# BL600CommunicationBoard.net
KiCad netlist of a schematic drawn in EAGLE
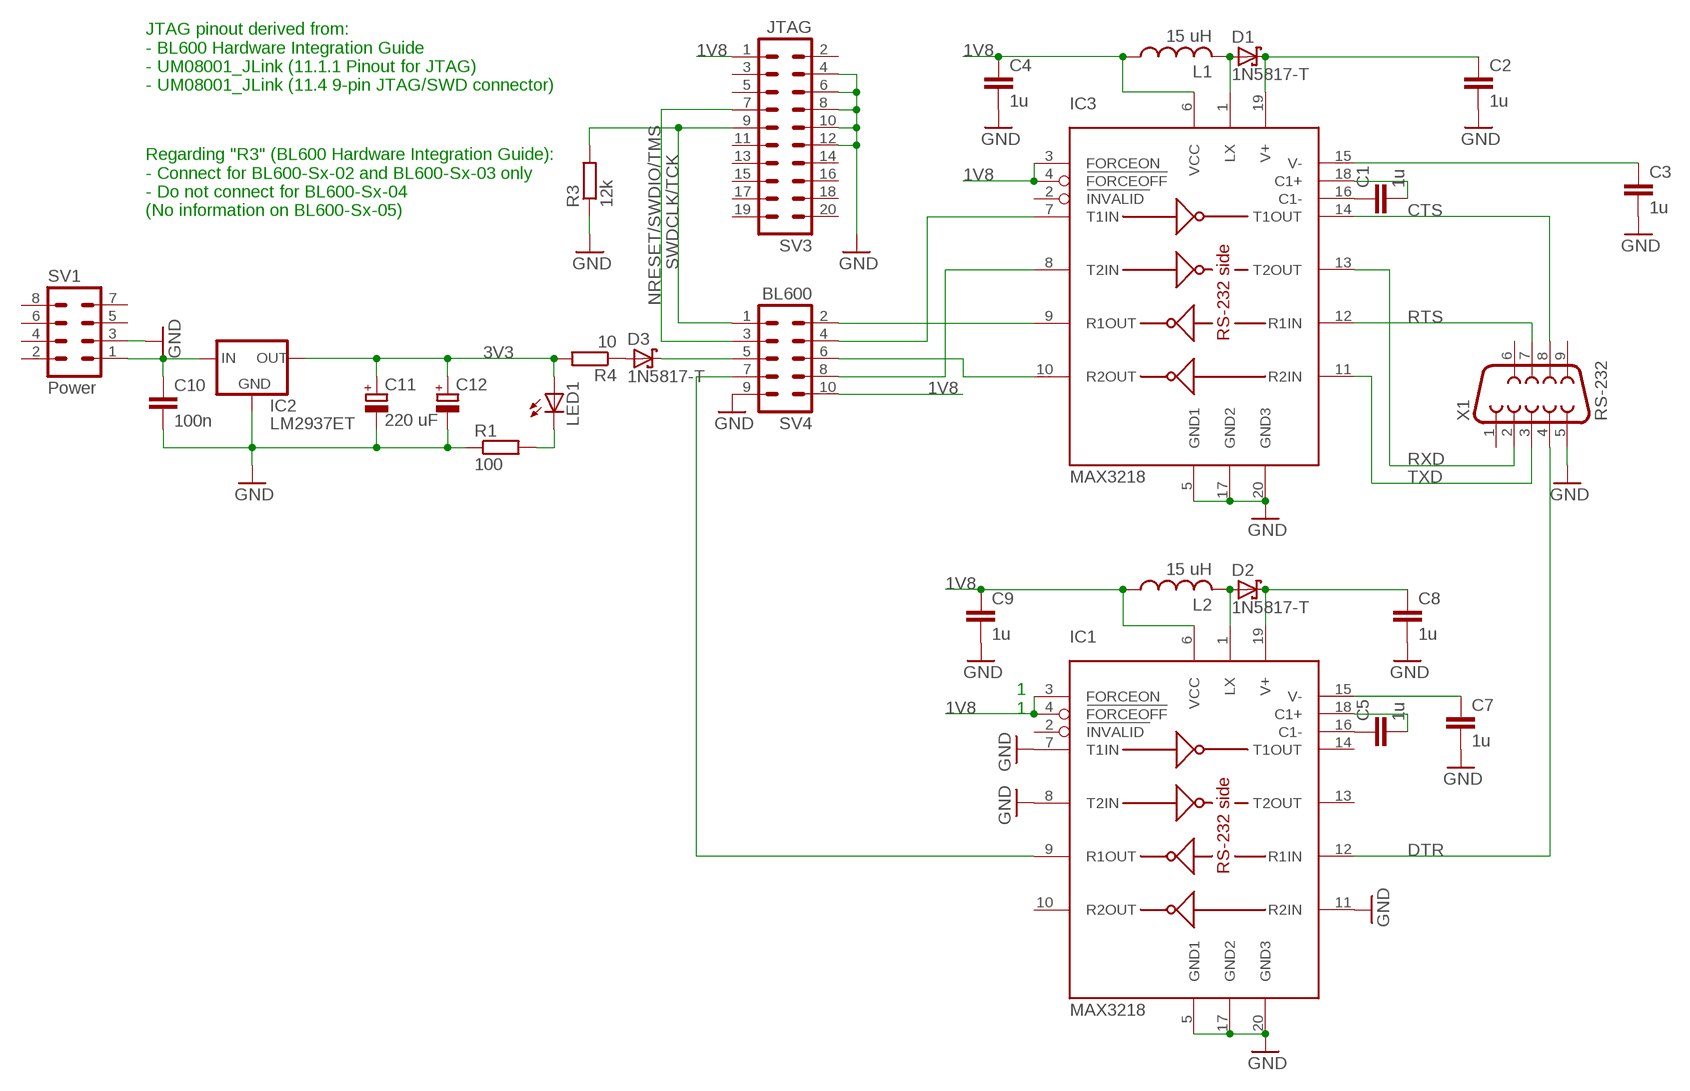
[diagram p0: schematic, sheet 1]

(export (version "E")
  (design (tool "Eeschema 10.0.6"))
  (components
    (comp (ref "C1")
      (value "1u")
      (footprint "eagle-import:C050-025X075")
      (libsource (lib "eagle-import") (part "C-EU050-025X075"))
    )
    (comp (ref "C2")
      (value "1u")
      (footprint "eagle-import:C050-025X075")
      (libsource (lib "eagle-import") (part "C-EU050-025X075"))
    )
    (comp (ref "C3")
      (value "1u")
      (footprint "eagle-import:C050-025X075")
      (libsource (lib "eagle-import") (part "C-EU050-025X075"))
    )
    (comp (ref "C4")
      (value "1u")
      (footprint "eagle-import:C050-025X075")
      (libsource (lib "eagle-import") (part "C-EU050-025X075"))
    )
    (comp (ref "C5")
      (value "1u")
      (footprint "eagle-import:C050-025X075")
      (libsource (lib "eagle-import") (part "C-EU050-025X075"))
    )
    (comp (ref "C7")
      (value "1u")
      (footprint "eagle-import:C050-025X075")
      (libsource (lib "eagle-import") (part "C-EU050-025X075"))
    )
    (comp (ref "C8")
      (value "1u")
      (footprint "eagle-import:C050-025X075")
      (libsource (lib "eagle-import") (part "C-EU050-025X075"))
    )
    (comp (ref "C9")
      (value "1u")
      (footprint "eagle-import:C050-025X075")
      (libsource (lib "eagle-import") (part "C-EU050-025X075"))
    )
    (comp (ref "C10")
      (value "100n")
      (footprint "eagle-import:C050-025X075")
      (libsource (lib "eagle-import") (part "C-EU050-025X075"))
    )
    (comp (ref "C11")
      (value "220 uF")
      (footprint "eagle-import:E2,5-6")
      (libsource (lib "eagle-import") (part "CPOL-EUE2.5-6"))
    )
    (comp (ref "C12")
      (value "CPOL-EUE3.5-8")
      (footprint "eagle-import:E3,5-8")
      (libsource (lib "eagle-import") (part "CPOL-EUE3.5-8"))
    )
    (comp (ref "D1")
      (value "1N5817-T")
      (footprint "eagle-import:DO41-7.6")
      (libsource (lib "eagle-import") (part "1N5817-T"))
    )
    (comp (ref "D2")
      (value "1N5817-T")
      (footprint "eagle-import:DO41-7.6")
      (libsource (lib "eagle-import") (part "1N5817-T"))
    )
    (comp (ref "D3")
      (value "1N5817-T")
      (footprint "eagle-import:DO41-7.6")
      (libsource (lib "eagle-import") (part "1N5817-T"))
    )
    (comp (ref "IC1")
      (value "MAX3218")
      (footprint "eagle-import:DIL20")
      (libsource (lib "eagle-import") (part "MAX3218"))
    )
    (comp (ref "IC2")
      (value "LM2937ET")
      (footprint "eagle-import:78XXS")
      (libsource (lib "eagle-import") (part "78XXS"))
    )
    (comp (ref "IC3")
      (value "MAX3218")
      (footprint "eagle-import:DIL20")
      (libsource (lib "eagle-import") (part "MAX3218"))
    )
    (comp (ref "L1")
      (value "15 uH")
      (footprint "eagle-import:L1812")
      (libsource (lib "eagle-import") (part "L-USL1812"))
    )
    (comp (ref "L2")
      (value "15 uH")
      (footprint "eagle-import:L1812")
      (libsource (lib "eagle-import") (part "L-USL1812"))
    )
    (comp (ref "LED1")
      (value "LED3MM")
      (footprint "eagle-import:LED3MM")
      (libsource (lib "eagle-import") (part "LED3MM"))
    )
    (comp (ref "R1")
      (value "100")
      (footprint "eagle-import:0207_10")
      (libsource (lib "eagle-import") (part "R-EU_0207/10"))
    )
    (comp (ref "R3")
      (value "12k")
      (footprint "eagle-import:0207_10")
      (libsource (lib "eagle-import") (part "R-EU_0207/10"))
    )
    (comp (ref "R4")
      (value "10")
      (footprint "eagle-import:0207_10")
      (libsource (lib "eagle-import") (part "R-EU_0207/10"))
    )
    (comp (ref "SV1")
      (value "Power")
      (footprint "eagle-import:MA04-2")
      (libsource (lib "eagle-import") (part "MA04-2"))
    )
    (comp (ref "SV3")
      (value "JTAG")
      (footprint "eagle-import:MA10-2")
      (libsource (lib "eagle-import") (part "MA10-2"))
    )
    (comp (ref "SV4")
      (value "BL600")
      (footprint "eagle-import:MA05-2")
      (libsource (lib "eagle-import") (part "MA05-2"))
    )
    (comp (ref "X1")
      (value "RS-232")
      (footprint "eagle-import:F09VP")
      (libsource (lib "eagle-import") (part "F09VP"))
    )
  )
  (nets
    (net (code "1") (name "/1V8") (class "Default")
      (node (ref "C4") (pin "1") (pinfunction "1_1") (pintype "passive"))
      (node (ref "C9") (pin "1") (pinfunction "1_1") (pintype "passive"))
      (node (ref "IC1") (pin "3") (pinfunction "FORCEON_3") (pintype "input"))
      (node (ref "IC1") (pin "4") (pinfunction "FORCEOFF_4") (pintype "input"))
      (node (ref "IC1") (pin "6") (pinfunction "VCC_6") (pintype "power_in"))
      (node (ref "IC3") (pin "3") (pinfunction "FORCEON_3") (pintype "input"))
      (node (ref "IC3") (pin "4") (pinfunction "FORCEOFF_4") (pintype "input"))
      (node (ref "IC3") (pin "6") (pinfunction "VCC_6") (pintype "power_in"))
      (node (ref "L1") (pin "1") (pinfunction "1_1") (pintype "passive"))
      (node (ref "L2") (pin "1") (pinfunction "1_1") (pintype "passive"))
      (node (ref "SV3") (pin "1") (pinfunction "1_1") (pintype "passive"))
      (node (ref "SV4") (pin "10") (pinfunction "10_10") (pintype "passive"))
    )
    (net (code "2") (name "/3V3") (class "Default")
      (node (ref "C11") (pin "+") (pinfunction "+_+") (pintype "passive"))
      (node (ref "C12") (pin "+") (pinfunction "+_+") (pintype "passive"))
      (node (ref "IC2") (pin "OUT") (pinfunction "OUT_OUT") (pintype "passive"))
      (node (ref "LED1") (pin "A") (pinfunction "A_A") (pintype "passive"))
      (node (ref "R4") (pin "2") (pinfunction "2_2") (pintype "passive"))
    )
    (net (code "3") (name "/CTS") (class "Default")
      (node (ref "IC3") (pin "14") (pinfunction "T1OUT_14") (pintype "output"))
      (node (ref "X1") (pin "8") (pinfunction "8_8") (pintype "passive"))
    )
    (net (code "4") (name "/DTR") (class "Default")
      (node (ref "IC1") (pin "12") (pinfunction "R1IN_12") (pintype "input"))
      (node (ref "X1") (pin "4") (pinfunction "4_4") (pintype "passive"))
    )
    (net (code "5") (name "/NRESET{slash}SWDIO{slash}TMS") (class "Default")
      (node (ref "SV3") (pin "7") (pinfunction "7_7") (pintype "passive"))
      (node (ref "SV4") (pin "3") (pinfunction "3_3") (pintype "passive"))
    )
    (net (code "6") (name "/RTS") (class "Default")
      (node (ref "IC3") (pin "12") (pinfunction "R1IN_12") (pintype "input"))
      (node (ref "X1") (pin "7") (pinfunction "7_7") (pintype "passive"))
    )
    (net (code "7") (name "/RXD") (class "Default")
      (node (ref "IC3") (pin "13") (pinfunction "T2OUT_13") (pintype "output"))
      (node (ref "X1") (pin "2") (pinfunction "2_2") (pintype "passive"))
    )
    (net (code "8") (name "/SWDCLK{slash}TCK") (class "Default")
      (node (ref "R3") (pin "2") (pinfunction "2_2") (pintype "passive"))
      (node (ref "SV3") (pin "9") (pinfunction "9_9") (pintype "passive"))
      (node (ref "SV4") (pin "1") (pinfunction "1_1") (pintype "passive"))
    )
    (net (code "9") (name "/TXD") (class "Default")
      (node (ref "IC3") (pin "11") (pinfunction "R2IN_11") (pintype "input"))
      (node (ref "X1") (pin "3") (pinfunction "3_3") (pintype "passive"))
    )
    (net (code "10") (name "GND") (class "Default")
      (node (ref "C10") (pin "2") (pinfunction "2_2") (pintype "passive"))
      (node (ref "C11") (pin "-") (pinfunction "-_-") (pintype "passive"))
      (node (ref "C12") (pin "-") (pinfunction "-_-") (pintype "passive"))
      (node (ref "C2") (pin "2") (pinfunction "2_2") (pintype "passive"))
      (node (ref "C3") (pin "2") (pinfunction "2_2") (pintype "passive"))
      (node (ref "C4") (pin "2") (pinfunction "2_2") (pintype "passive"))
      (node (ref "C7") (pin "2") (pinfunction "2_2") (pintype "passive"))
      (node (ref "C8") (pin "2") (pinfunction "2_2") (pintype "passive"))
      (node (ref "C9") (pin "2") (pinfunction "2_2") (pintype "passive"))
      (node (ref "IC1") (pin "11") (pinfunction "R2IN_11") (pintype "input"))
      (node (ref "IC1") (pin "17") (pinfunction "GND2_17") (pintype "power_in"))
      (node (ref "IC1") (pin "20") (pinfunction "GND3_20") (pintype "power_in"))
      (node (ref "IC1") (pin "5") (pinfunction "GND1_5") (pintype "power_in"))
      (node (ref "IC1") (pin "7") (pinfunction "T1IN_7") (pintype "input"))
      (node (ref "IC1") (pin "8") (pinfunction "T2IN_8") (pintype "input"))
      (node (ref "IC2") (pin "GND") (pinfunction "GND_GND") (pintype "input"))
      (node (ref "IC3") (pin "17") (pinfunction "GND2_17") (pintype "power_in"))
      (node (ref "IC3") (pin "20") (pinfunction "GND3_20") (pintype "power_in"))
      (node (ref "IC3") (pin "5") (pinfunction "GND1_5") (pintype "power_in"))
      (node (ref "R1") (pin "1") (pinfunction "1_1") (pintype "passive"))
      (node (ref "R3") (pin "1") (pinfunction "1_1") (pintype "passive"))
      (node (ref "SV1") (pin "3") (pinfunction "3_3") (pintype "passive"))
      (node (ref "SV3") (pin "10") (pinfunction "10_10") (pintype "passive"))
      (node (ref "SV3") (pin "12") (pinfunction "12_12") (pintype "passive"))
      (node (ref "SV3") (pin "4") (pinfunction "4_4") (pintype "passive"))
      (node (ref "SV3") (pin "6") (pinfunction "6_6") (pintype "passive"))
      (node (ref "SV3") (pin "8") (pinfunction "8_8") (pintype "passive"))
      (node (ref "SV4") (pin "9") (pinfunction "9_9") (pintype "passive"))
      (node (ref "X1") (pin "5") (pinfunction "5_5") (pintype "passive"))
    )
    (net (code "11") (name "Net-(C10-Pad1)") (class "Default")
      (node (ref "C10") (pin "1") (pinfunction "1_1") (pintype "passive"))
      (node (ref "IC2") (pin "IN") (pinfunction "IN_IN") (pintype "input"))
      (node (ref "SV1") (pin "1") (pinfunction "1_1") (pintype "passive"))
    )
    (net (code "12") (name "Net-(D3-PadA)") (class "Default")
      (node (ref "D3") (pin "A") (pinfunction "A_A") (pintype "passive"))
      (node (ref "R4") (pin "1") (pinfunction "1_1") (pintype "passive"))
    )
    (net (code "13") (name "Net-(D3-PadC)") (class "Default")
      (node (ref "D3") (pin "C") (pinfunction "C_C") (pintype "passive"))
      (node (ref "SV4") (pin "5") (pinfunction "5_5") (pintype "passive"))
    )
    (net (code "14") (name "Net-(IC1-C1+)") (class "Default")
      (node (ref "C5") (pin "2") (pinfunction "2_2") (pintype "passive"))
      (node (ref "IC1") (pin "18") (pinfunction "C1+_18") (pintype "bidirectional"))
    )
    (net (code "15") (name "Net-(IC1-C1-)") (class "Default")
      (node (ref "C5") (pin "1") (pinfunction "1_1") (pintype "passive"))
      (node (ref "IC1") (pin "16") (pinfunction "C1-_16") (pintype "bidirectional"))
    )
    (net (code "16") (name "Net-(IC1-LX)") (class "Default")
      (node (ref "D2") (pin "A") (pinfunction "A_A") (pintype "passive"))
      (node (ref "IC1") (pin "1") (pinfunction "LX_1") (pintype "bidirectional"))
      (node (ref "L2") (pin "2") (pinfunction "2_2") (pintype "passive"))
    )
    (net (code "17") (name "Net-(IC1-R1OUT)") (class "Default")
      (node (ref "IC1") (pin "9") (pinfunction "R1OUT_9") (pintype "output"))
      (node (ref "SV4") (pin "7") (pinfunction "7_7") (pintype "passive"))
    )
    (net (code "18") (name "Net-(IC1-V+)") (class "Default")
      (node (ref "C8") (pin "1") (pinfunction "1_1") (pintype "passive"))
      (node (ref "D2") (pin "C") (pinfunction "C_C") (pintype "passive"))
      (node (ref "IC1") (pin "19") (pinfunction "V+_19") (pintype "bidirectional"))
    )
    (net (code "19") (name "Net-(IC1-V-)") (class "Default")
      (node (ref "C7") (pin "1") (pinfunction "1_1") (pintype "passive"))
      (node (ref "IC1") (pin "15") (pinfunction "V-_15") (pintype "bidirectional"))
    )
    (net (code "20") (name "Net-(IC3-C1+)") (class "Default")
      (node (ref "C1") (pin "2") (pinfunction "2_2") (pintype "passive"))
      (node (ref "IC3") (pin "18") (pinfunction "C1+_18") (pintype "bidirectional"))
    )
    (net (code "21") (name "Net-(IC3-C1-)") (class "Default")
      (node (ref "C1") (pin "1") (pinfunction "1_1") (pintype "passive"))
      (node (ref "IC3") (pin "16") (pinfunction "C1-_16") (pintype "bidirectional"))
    )
    (net (code "22") (name "Net-(IC3-LX)") (class "Default")
      (node (ref "D1") (pin "A") (pinfunction "A_A") (pintype "passive"))
      (node (ref "IC3") (pin "1") (pinfunction "LX_1") (pintype "bidirectional"))
      (node (ref "L1") (pin "2") (pinfunction "2_2") (pintype "passive"))
    )
    (net (code "23") (name "Net-(IC3-R1OUT)") (class "Default")
      (node (ref "IC3") (pin "9") (pinfunction "R1OUT_9") (pintype "output"))
      (node (ref "SV4") (pin "2") (pinfunction "2_2") (pintype "passive"))
    )
    (net (code "24") (name "Net-(IC3-R2OUT)") (class "Default")
      (node (ref "IC3") (pin "10") (pinfunction "R2OUT_10") (pintype "output"))
      (node (ref "SV4") (pin "6") (pinfunction "6_6") (pintype "passive"))
    )
    (net (code "25") (name "Net-(IC3-T1IN)") (class "Default")
      (node (ref "IC3") (pin "7") (pinfunction "T1IN_7") (pintype "input"))
      (node (ref "SV4") (pin "4") (pinfunction "4_4") (pintype "passive"))
    )
    (net (code "26") (name "Net-(IC3-T2IN)") (class "Default")
      (node (ref "IC3") (pin "8") (pinfunction "T2IN_8") (pintype "input"))
      (node (ref "SV4") (pin "8") (pinfunction "8_8") (pintype "passive"))
    )
    (net (code "27") (name "Net-(IC3-V+)") (class "Default")
      (node (ref "C2") (pin "1") (pinfunction "1_1") (pintype "passive"))
      (node (ref "D1") (pin "C") (pinfunction "C_C") (pintype "passive"))
      (node (ref "IC3") (pin "19") (pinfunction "V+_19") (pintype "bidirectional"))
    )
    (net (code "28") (name "Net-(IC3-V-)") (class "Default")
      (node (ref "C3") (pin "1") (pinfunction "1_1") (pintype "passive"))
      (node (ref "IC3") (pin "15") (pinfunction "V-_15") (pintype "bidirectional"))
    )
    (net (code "29") (name "Net-(LED1-C)") (class "Default")
      (node (ref "LED1") (pin "K") (pinfunction "C_K") (pintype "passive"))
      (node (ref "R1") (pin "2") (pinfunction "2_2") (pintype "passive"))
    )
    (net (code "30") (name "unconnected-(IC1-INVALID-Pad2)") (class "Default")
      (node (ref "IC1") (pin "2") (pinfunction "INVALID_2") (pintype "output"))
    )
    (net (code "31") (name "unconnected-(IC1-R2OUT-Pad10)") (class "Default")
      (node (ref "IC1") (pin "10") (pinfunction "R2OUT_10") (pintype "output"))
    )
    (net (code "32") (name "unconnected-(IC1-T1OUT-Pad14)") (class "Default")
      (node (ref "IC1") (pin "14") (pinfunction "T1OUT_14") (pintype "output"))
    )
    (net (code "33") (name "unconnected-(IC1-T2OUT-Pad13)") (class "Default")
      (node (ref "IC1") (pin "13") (pinfunction "T2OUT_13") (pintype "output"))
    )
    (net (code "34") (name "unconnected-(IC3-INVALID-Pad2)") (class "Default")
      (node (ref "IC3") (pin "2") (pinfunction "INVALID_2") (pintype "output"))
    )
    (net (code "35") (name "unconnected-(SV1-Pad2)") (class "Default")
      (node (ref "SV1") (pin "2") (pinfunction "2_2") (pintype "passive"))
    )
    (net (code "36") (name "unconnected-(SV1-Pad4)") (class "Default")
      (node (ref "SV1") (pin "4") (pinfunction "4_4") (pintype "passive"))
    )
    (net (code "37") (name "unconnected-(SV1-Pad5)") (class "Default")
      (node (ref "SV1") (pin "5") (pinfunction "5_5") (pintype "passive"))
    )
    (net (code "38") (name "unconnected-(SV1-Pad6)") (class "Default")
      (node (ref "SV1") (pin "6") (pinfunction "6_6") (pintype "passive"))
    )
    (net (code "39") (name "unconnected-(SV1-Pad7)") (class "Default")
      (node (ref "SV1") (pin "7") (pinfunction "7_7") (pintype "passive"))
    )
    (net (code "40") (name "unconnected-(SV1-Pad8)") (class "Default")
      (node (ref "SV1") (pin "8") (pinfunction "8_8") (pintype "passive"))
    )
    (net (code "41") (name "unconnected-(SV3-Pad2)") (class "Default")
      (node (ref "SV3") (pin "2") (pinfunction "2_2") (pintype "passive"))
    )
    (net (code "42") (name "unconnected-(SV3-Pad3)") (class "Default")
      (node (ref "SV3") (pin "3") (pinfunction "3_3") (pintype "passive"))
    )
    (net (code "43") (name "unconnected-(SV3-Pad5)") (class "Default")
      (node (ref "SV3") (pin "5") (pinfunction "5_5") (pintype "passive"))
    )
    (net (code "44") (name "unconnected-(SV3-Pad11)") (class "Default")
      (node (ref "SV3") (pin "11") (pinfunction "11_11") (pintype "passive"))
    )
    (net (code "45") (name "unconnected-(SV3-Pad13)") (class "Default")
      (node (ref "SV3") (pin "13") (pinfunction "13_13") (pintype "passive"))
    )
    (net (code "46") (name "unconnected-(SV3-Pad14)") (class "Default")
      (node (ref "SV3") (pin "14") (pinfunction "14_14") (pintype "passive"))
    )
    (net (code "47") (name "unconnected-(SV3-Pad15)") (class "Default")
      (node (ref "SV3") (pin "15") (pinfunction "15_15") (pintype "passive"))
    )
    (net (code "48") (name "unconnected-(SV3-Pad16)") (class "Default")
      (node (ref "SV3") (pin "16") (pinfunction "16_16") (pintype "passive"))
    )
    (net (code "49") (name "unconnected-(SV3-Pad17)") (class "Default")
      (node (ref "SV3") (pin "17") (pinfunction "17_17") (pintype "passive"))
    )
    (net (code "50") (name "unconnected-(SV3-Pad18)") (class "Default")
      (node (ref "SV3") (pin "18") (pinfunction "18_18") (pintype "passive"))
    )
    (net (code "51") (name "unconnected-(SV3-Pad19)") (class "Default")
      (node (ref "SV3") (pin "19") (pinfunction "19_19") (pintype "passive"))
    )
    (net (code "52") (name "unconnected-(SV3-Pad20)") (class "Default")
      (node (ref "SV3") (pin "20") (pinfunction "20_20") (pintype "passive"))
    )
    (net (code "53") (name "unconnected-(X1-Pad1)") (class "Default")
      (node (ref "X1") (pin "1") (pinfunction "1_1") (pintype "passive"))
    )
    (net (code "54") (name "unconnected-(X1-Pad6)") (class "Default")
      (node (ref "X1") (pin "6") (pinfunction "6_6") (pintype "passive"))
    )
    (net (code "55") (name "unconnected-(X1-Pad9)") (class "Default")
      (node (ref "X1") (pin "9") (pinfunction "9_9") (pintype "passive"))
    )
  )
)
